# turkin_ivt23_1d_list1.net
KiCad netlist of a schematic drawn in Altium Designer
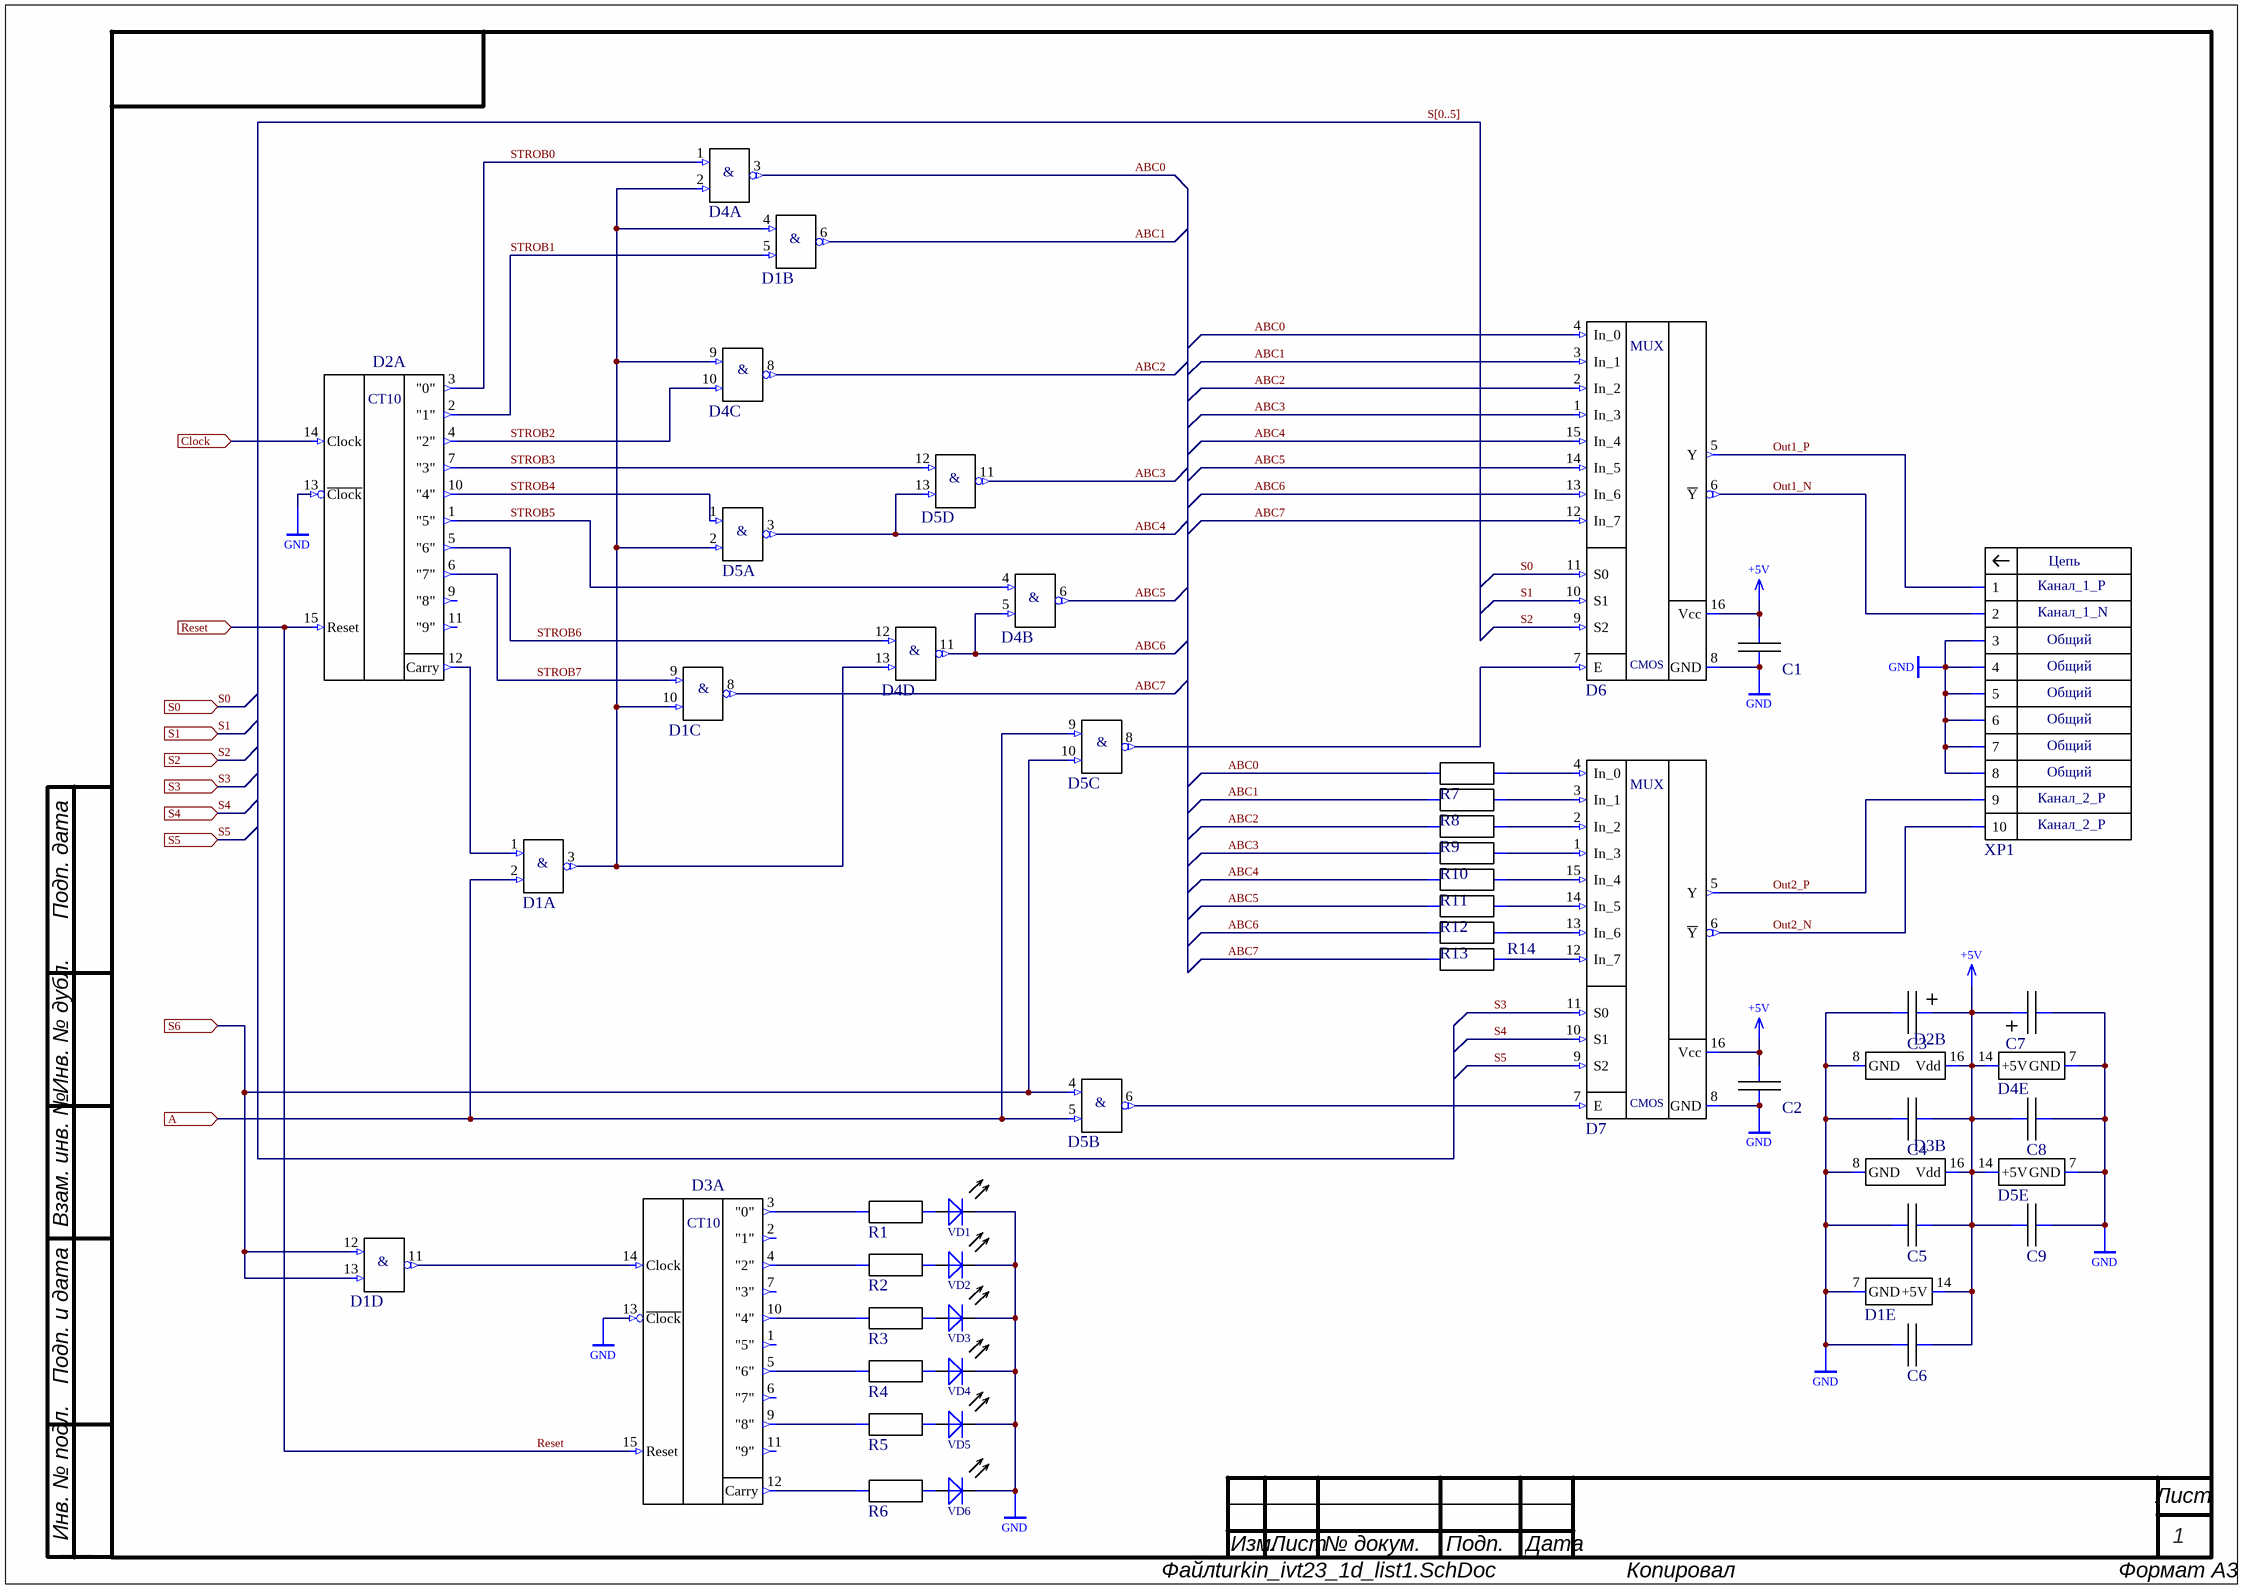
[diagram p0: turkin_ivt23_1d_list1.SchDoc]

(export (version "E")
  (design (tool "Eeschema 10.0.6"))
  (components
    (comp (ref "C1")
      (value "~")
      (footprint "0805_N")
      (description "Чип конденсатор 0805 Н90 ряд Е6")
      (fields
        (field (name "MANUFACTURER") "ООО \"Кулон\"")
        (field (name "TOLERANCE") "+80%-20%")
        (field (name "CREATED_BY") "Желобаев")
      )
      (libsource (lib "Int_Library_for_Lessons_3") (part "К10-79_0805_Н90"))
    )
    (comp (ref "C2")
      (value "~")
      (footprint "0805_N")
      (description "Чип конденсатор 0805 Н90 ряд Е6")
      (fields
        (field (name "MANUFACTURER") "ООО \"Кулон\"")
        (field (name "TOLERANCE") "+80%-20%")
        (field (name "CREATED_BY") "Желобаев")
      )
      (libsource (lib "Int_Library_for_Lessons_3") (part "К10-79_0805_Н90"))
    )
    (comp (ref "C3")
      (value "C")
      (footprint "C-Tantal")
      (description "К53-65 Конденсатор танталовый C(6032) 0,47-100 мкФ")
      (fields
        (field (name "VOLTAGE") "16В")
        (field (name "MANUFACTURER") "ОАО \"Элеконд\"")
        (field (name "CREATED_BY") "Желобаев")
      )
      (libsource (lib "Int_Library_for_Lessons_3") (part "K53-65_C_10%"))
    )
    (comp (ref "C4")
      (value "~")
      (footprint "0805_N")
      (description "Чип конденсатор 0805 Н90 ряд Е6")
      (fields
        (field (name "MANUFACTURER") "ООО \"Кулон\"")
        (field (name "TOLERANCE") "+80%-20%")
        (field (name "CREATED_BY") "Желобаев")
      )
      (libsource (lib "Int_Library_for_Lessons_3") (part "К10-79_0805_Н90"))
    )
    (comp (ref "C5")
      (value "~")
      (footprint "0805_N")
      (description "Чип конденсатор 0805 Н90 ряд Е6")
      (fields
        (field (name "MANUFACTURER") "ООО \"Кулон\"")
        (field (name "TOLERANCE") "+80%-20%")
        (field (name "CREATED_BY") "Желобаев")
      )
      (libsource (lib "Int_Library_for_Lessons_3") (part "К10-79_0805_Н90"))
    )
    (comp (ref "C6")
      (value "~")
      (footprint "0805_N")
      (description "Чип конденсатор 0805 Н90 ряд Е6")
      (fields
        (field (name "MANUFACTURER") "ООО \"Кулон\"")
        (field (name "TOLERANCE") "+80%-20%")
        (field (name "CREATED_BY") "Желобаев")
      )
      (libsource (lib "Int_Library_for_Lessons_3") (part "К10-79_0805_Н90"))
    )
    (comp (ref "C7")
      (value "C")
      (footprint "C-Tantal")
      (description "К53-65 Конденсатор танталовый C(6032) 0,47-100 мкФ")
      (fields
        (field (name "VOLTAGE") "16В")
        (field (name "MANUFACTURER") "ОАО \"Элеконд\"")
        (field (name "CREATED_BY") "Желобаев")
      )
      (libsource (lib "Int_Library_for_Lessons_3") (part "K53-65_C_10%"))
    )
    (comp (ref "C8")
      (value "~")
      (footprint "0805_N")
      (description "Чип конденсатор 0805 Н90 ряд Е6")
      (fields
        (field (name "MANUFACTURER") "ООО \"Кулон\"")
        (field (name "TOLERANCE") "+80%-20%")
        (field (name "CREATED_BY") "Желобаев")
      )
      (libsource (lib "Int_Library_for_Lessons_3") (part "К10-79_0805_Н90"))
    )
    (comp (ref "C9")
      (value "~")
      (footprint "0805_N")
      (description "Чип конденсатор 0805 Н90 ряд Е6")
      (fields
        (field (name "MANUFACTURER") "ООО \"Кулон\"")
        (field (name "TOLERANCE") "+80%-20%")
        (field (name "CREATED_BY") "Желобаев")
      )
      (libsource (lib "Int_Library_for_Lessons_3") (part "К10-79_0805_Н90"))
    )
    (comp (ref "D1")
      (value "74AC00SC")
      (footprint "SO14-N")
      (description "4 элемента 2И-НЕ TTL SOIC-14")
      (fields (field (name "MANUFACTURER") "ON Semiconductor") (field (name "CREATED_BY") "Желобаев"))
      (libsource (lib "Int_Library_for_Lessons_3") (part "74AC00SC"))
    )
    (comp (ref "D2")
      (value "DIP-16")
      (footprint "DIP16")
      (description "Декадный счетчик c 10 декодированными выходами")
      (fields (field (name "MANUFACTURER") "STMicroelectronics") (field (name "CREATED_BY") "Желобаев"))
      (libsource (lib "Int_Library_for_Lessons_3") (part "HCF4017BEY"))
    )
    (comp (ref "D3")
      (value "DIP-16")
      (footprint "DIP16")
      (description "Декадный счетчик c 10 декодированными выходами")
      (fields (field (name "MANUFACTURER") "STMicroelectronics") (field (name "CREATED_BY") "Желобаев"))
      (libsource (lib "Int_Library_for_Lessons_3") (part "HCF4017BEY"))
    )
    (comp (ref "D4")
      (value "74AC00SC")
      (footprint "SO14-N")
      (description "4 элемента 2И-НЕ TTL SOIC-14")
      (fields (field (name "MANUFACTURER") "ON Semiconductor") (field (name "CREATED_BY") "Желобаев"))
      (libsource (lib "Int_Library_for_Lessons_3") (part "74AC00SC"))
    )
    (comp (ref "D5")
      (value "74AC00SC")
      (footprint "SO14-N")
      (description "4 элемента 2И-НЕ TTL SOIC-14")
      (fields (field (name "MANUFACTURER") "ON Semiconductor") (field (name "CREATED_BY") "Желобаев"))
      (libsource (lib "Int_Library_for_Lessons_3") (part "74AC00SC"))
    )
    (comp (ref "D6")
      (value "SOIC-16")
      (footprint "SO16-N")
      (description "мультиплексор 8 канальный CMOS")
      (fields (field (name "MANUFACTURER") "NXP Semiconductors") (field (name "CREATED_BY") "Желобаев"))
      (libsource (lib "Int_Library_for_Lessons_3") (part "74HC151D"))
    )
    (comp (ref "D7")
      (value "SOIC-16")
      (footprint "SO16-N")
      (description "мультиплексор 8 канальный CMOS")
      (fields (field (name "MANUFACTURER") "NXP Semiconductors") (field (name "CREATED_BY") "Желобаев"))
      (libsource (lib "Int_Library_for_Lessons_3") (part "74HC151D"))
    )
    (comp (ref "R1")
      (value "0805")
      (footprint "RES_0805_2012_N")
      (description "Резистор от 0,75 Ом до 2 МОм")
      (fields
        (field (name "MANUFACTURER") "ОАО \"НПО \"Эркон\"")
        (field (name "TOLERANCE") "5%")
        (field (name "CREATED_BY") "Желобаев")
      )
      (libsource (lib "Int_Library_for_Lessons_3") (part "Р1-12-0,125-5%"))
    )
    (comp (ref "R2")
      (value "0805")
      (footprint "RES_0805_2012_N")
      (description "Резистор от 0,75 Ом до 2 МОм")
      (fields
        (field (name "MANUFACTURER") "ОАО \"НПО \"Эркон\"")
        (field (name "TOLERANCE") "5%")
        (field (name "CREATED_BY") "Желобаев")
      )
      (libsource (lib "Int_Library_for_Lessons_3") (part "Р1-12-0,125-5%"))
    )
    (comp (ref "R3")
      (value "0805")
      (footprint "RES_0805_2012_N")
      (description "Резистор от 0,75 Ом до 2 МОм")
      (fields
        (field (name "MANUFACTURER") "ОАО \"НПО \"Эркон\"")
        (field (name "TOLERANCE") "5%")
        (field (name "CREATED_BY") "Желобаев")
      )
      (libsource (lib "Int_Library_for_Lessons_3") (part "Р1-12-0,125-5%"))
    )
    (comp (ref "R4")
      (value "0805")
      (footprint "RES_0805_2012_N")
      (description "Резистор от 0,75 Ом до 2 МОм")
      (fields
        (field (name "MANUFACTURER") "ОАО \"НПО \"Эркон\"")
        (field (name "TOLERANCE") "5%")
        (field (name "CREATED_BY") "Желобаев")
      )
      (libsource (lib "Int_Library_for_Lessons_3") (part "Р1-12-0,125-5%"))
    )
    (comp (ref "R5")
      (value "0805")
      (footprint "RES_0805_2012_N")
      (description "Резистор от 0,75 Ом до 2 МОм")
      (fields
        (field (name "MANUFACTURER") "ОАО \"НПО \"Эркон\"")
        (field (name "TOLERANCE") "5%")
        (field (name "CREATED_BY") "Желобаев")
      )
      (libsource (lib "Int_Library_for_Lessons_3") (part "Р1-12-0,125-5%"))
    )
    (comp (ref "R6")
      (value "0805")
      (footprint "RES_0805_2012_N")
      (description "Резистор от 0,75 Ом до 2 МОм")
      (fields
        (field (name "MANUFACTURER") "ОАО \"НПО \"Эркон\"")
        (field (name "TOLERANCE") "5%")
        (field (name "CREATED_BY") "Желобаев")
      )
      (libsource (lib "Int_Library_for_Lessons_3") (part "Р1-12-0,125-5%"))
    )
    (comp (ref "R7")
      (value "0805")
      (footprint "RES_0805_2012_N")
      (description "Резистор от 0,75 Ом до 2 МОм")
      (fields
        (field (name "MANUFACTURER") "ОАО \"НПО \"Эркон\"")
        (field (name "TOLERANCE") "5%")
        (field (name "CREATED_BY") "Желобаев")
      )
      (libsource (lib "Int_Library_for_Lessons_3") (part "Р1-12-0,125-5%"))
    )
    (comp (ref "R8")
      (value "0805")
      (footprint "RES_0805_2012_N")
      (description "Резистор от 0,75 Ом до 2 МОм")
      (fields
        (field (name "MANUFACTURER") "ОАО \"НПО \"Эркон\"")
        (field (name "TOLERANCE") "5%")
        (field (name "CREATED_BY") "Желобаев")
      )
      (libsource (lib "Int_Library_for_Lessons_3") (part "Р1-12-0,125-5%"))
    )
    (comp (ref "R9")
      (value "0805")
      (footprint "RES_0805_2012_N")
      (description "Резистор от 0,75 Ом до 2 МОм")
      (fields
        (field (name "MANUFACTURER") "ОАО \"НПО \"Эркон\"")
        (field (name "TOLERANCE") "5%")
        (field (name "CREATED_BY") "Желобаев")
      )
      (libsource (lib "Int_Library_for_Lessons_3") (part "Р1-12-0,125-5%"))
    )
    (comp (ref "R10")
      (value "0805")
      (footprint "RES_0805_2012_N")
      (description "Резистор от 0,75 Ом до 2 МОм")
      (fields
        (field (name "MANUFACTURER") "ОАО \"НПО \"Эркон\"")
        (field (name "TOLERANCE") "5%")
        (field (name "CREATED_BY") "Желобаев")
      )
      (libsource (lib "Int_Library_for_Lessons_3") (part "Р1-12-0,125-5%"))
    )
    (comp (ref "R11")
      (value "0805")
      (footprint "RES_0805_2012_N")
      (description "Резистор от 0,75 Ом до 2 МОм")
      (fields
        (field (name "MANUFACTURER") "ОАО \"НПО \"Эркон\"")
        (field (name "TOLERANCE") "5%")
        (field (name "CREATED_BY") "Желобаев")
      )
      (libsource (lib "Int_Library_for_Lessons_3") (part "Р1-12-0,125-5%"))
    )
    (comp (ref "R12")
      (value "0805")
      (footprint "RES_0805_2012_N")
      (description "Резистор от 0,75 Ом до 2 МОм")
      (fields
        (field (name "MANUFACTURER") "ОАО \"НПО \"Эркон\"")
        (field (name "TOLERANCE") "5%")
        (field (name "CREATED_BY") "Желобаев")
      )
      (libsource (lib "Int_Library_for_Lessons_3") (part "Р1-12-0,125-5%"))
    )
    (comp (ref "R13")
      (value "0805")
      (footprint "RES_0805_2012_N")
      (description "Резистор от 0,75 Ом до 2 МОм")
      (fields
        (field (name "MANUFACTURER") "ОАО \"НПО \"Эркон\"")
        (field (name "TOLERANCE") "5%")
        (field (name "CREATED_BY") "Желобаев")
      )
      (libsource (lib "Int_Library_for_Lessons_3") (part "Р1-12-0,125-5%"))
    )
    (comp (ref "R14")
      (value "0805")
      (footprint "RES_0805_2012_N")
      (description "Резистор от 0,75 Ом до 2 МОм")
      (fields
        (field (name "MANUFACTURER") "ОАО \"НПО \"Эркон\"")
        (field (name "TOLERANCE") "5%")
        (field (name "CREATED_BY") "Желобаев")
      )
      (libsource (lib "Int_Library_for_Lessons_3") (part "Р1-12-0,125-5%"))
    )
    (comp (ref "VD1")
      (value "521-9466")
      (footprint "added_pcb:521-9466")
      (description "Светодиод 5мм желтый")
      (libsource (lib "added_elements") (part "521-9466"))
    )
    (comp (ref "VD2")
      (value "521-9466")
      (footprint "added_pcb:521-9466")
      (description "Светодиод 5мм желтый")
      (libsource (lib "added_elements") (part "521-9466"))
    )
    (comp (ref "VD3")
      (value "521-9466")
      (footprint "added_pcb:521-9466")
      (description "Светодиод 5мм желтый")
      (libsource (lib "added_elements") (part "521-9466"))
    )
    (comp (ref "VD4")
      (value "521-9466")
      (footprint "added_pcb:521-9466")
      (description "Светодиод 5мм желтый")
      (libsource (lib "added_elements") (part "521-9466"))
    )
    (comp (ref "VD5")
      (value "521-9466")
      (footprint "added_pcb:521-9466")
      (description "Светодиод 5мм желтый")
      (libsource (lib "added_elements") (part "521-9466"))
    )
    (comp (ref "VD6")
      (value "521-9466")
      (footprint "added_pcb:521-9466")
      (description "Светодиод 5мм желтый")
      (libsource (lib "added_elements") (part "521-9466"))
    )
    (comp (ref "XP1")
      (value "TE_1-1634689-0")
      (footprint "BH-10R")
      (description "Вилка типа BH-10R угловая правая двухрядная 2х5х2.54")
      (fields (field (name "MANUFACTURER") "TE Connectivity") (field (name "CREATED_BY") "Желобаев"))
      (libsource (lib "Int_Library_for_Lessons_3") (part "TE_1-1634689-0"))
    )
  )
  (nets
    (net (code "1") (name "+5V") (class "Default")
      (node (ref "C1") (pin "2") (pinfunction "2_2") (pintype "passive"))
      (node (ref "C2") (pin "2") (pinfunction "2_2") (pintype "passive"))
      (node (ref "C3") (pin "+") (pinfunction "+_+") (pintype "passive"))
      (node (ref "C4") (pin "1") (pinfunction "1_1") (pintype "passive"))
      (node (ref "C5") (pin "1") (pinfunction "1_1") (pintype "passive"))
      (node (ref "C6") (pin "1") (pinfunction "1_1") (pintype "passive"))
      (node (ref "C7") (pin "+") (pinfunction "+_+") (pintype "passive"))
      (node (ref "C8") (pin "2") (pinfunction "2_2") (pintype "passive"))
      (node (ref "C9") (pin "2") (pinfunction "2_2") (pintype "passive"))
      (node (ref "D1") (pin "14") (pinfunction "+5V_14") (pintype "power_in"))
      (node (ref "D2") (pin "16") (pinfunction "Vdd_16") (pintype "power_in"))
      (node (ref "D3") (pin "16") (pinfunction "Vdd_16") (pintype "power_in"))
      (node (ref "D4") (pin "14") (pinfunction "+5V_14") (pintype "power_in"))
      (node (ref "D5") (pin "14") (pinfunction "+5V_14") (pintype "power_in"))
      (node (ref "D6") (pin "16") (pinfunction "Vcc_16") (pintype "power_in"))
      (node (ref "D7") (pin "16") (pinfunction "Vcc_16") (pintype "power_in"))
    )
    (net (code "2") (name "/A") (class "Default")
      (node (ref "D1") (pin "2") (pinfunction "In2_2") (pintype "input"))
      (node (ref "D5") (pin "5") (pinfunction "In2_5") (pintype "input"))
      (node (ref "D5") (pin "9") (pinfunction "In1_9") (pintype "input"))
    )
    (net (code "3") (name "/ABC0") (class "Default")
      (node (ref "D4") (pin "3") (pinfunction "Out_3") (pintype "output"))
      (node (ref "D6") (pin "4") (pinfunction "In_0_4") (pintype "input"))
      (node (ref "R7") (pin "1") (pinfunction "1_1") (pintype "passive"))
    )
    (net (code "4") (name "/ABC1") (class "Default")
      (node (ref "D1") (pin "6") (pinfunction "Out_6") (pintype "output"))
      (node (ref "D6") (pin "3") (pinfunction "In_1_3") (pintype "input"))
      (node (ref "R8") (pin "1") (pinfunction "1_1") (pintype "passive"))
    )
    (net (code "5") (name "/ABC2") (class "Default")
      (node (ref "D4") (pin "8") (pinfunction "Out_8") (pintype "output"))
      (node (ref "D6") (pin "2") (pinfunction "In_2_2") (pintype "input"))
      (node (ref "R9") (pin "1") (pinfunction "1_1") (pintype "passive"))
    )
    (net (code "6") (name "/ABC3") (class "Default")
      (node (ref "D5") (pin "11") (pinfunction "Out_11") (pintype "output"))
      (node (ref "D6") (pin "1") (pinfunction "In_3_1") (pintype "input"))
      (node (ref "R10") (pin "1") (pinfunction "1_1") (pintype "passive"))
    )
    (net (code "7") (name "/ABC4") (class "Default")
      (node (ref "D5") (pin "13") (pinfunction "In2_13") (pintype "input"))
      (node (ref "D5") (pin "3") (pinfunction "Out_3") (pintype "output"))
      (node (ref "D6") (pin "15") (pinfunction "In_4_15") (pintype "input"))
      (node (ref "R11") (pin "1") (pinfunction "1_1") (pintype "passive"))
    )
    (net (code "8") (name "/ABC5") (class "Default")
      (node (ref "D4") (pin "6") (pinfunction "Out_6") (pintype "output"))
      (node (ref "D6") (pin "14") (pinfunction "In_5_14") (pintype "input"))
      (node (ref "R12") (pin "1") (pinfunction "1_1") (pintype "passive"))
    )
    (net (code "9") (name "/ABC6") (class "Default")
      (node (ref "D4") (pin "11") (pinfunction "Out_11") (pintype "output"))
      (node (ref "D4") (pin "5") (pinfunction "In2_5") (pintype "input"))
      (node (ref "D6") (pin "13") (pinfunction "In_6_13") (pintype "input"))
      (node (ref "R13") (pin "1") (pinfunction "1_1") (pintype "passive"))
    )
    (net (code "10") (name "/ABC7") (class "Default")
      (node (ref "D1") (pin "8") (pinfunction "Out_8") (pintype "output"))
      (node (ref "D6") (pin "12") (pinfunction "In_7_12") (pintype "input"))
      (node (ref "R14") (pin "1") (pinfunction "1_1") (pintype "passive"))
    )
    (net (code "11") (name "/Clock") (class "Default")
      (node (ref "D2") (pin "14") (pinfunction "Clock_14") (pintype "input"))
    )
    (net (code "12") (name "/Out1_N") (class "Default")
      (node (ref "D6") (pin "6") (pinfunction "Y_6") (pintype "output"))
      (node (ref "XP1") (pin "2") (pinfunction "2_2") (pintype "passive"))
    )
    (net (code "13") (name "/Out1_P") (class "Default")
      (node (ref "D6") (pin "5") (pinfunction "Y_5") (pintype "output"))
      (node (ref "XP1") (pin "1") (pinfunction "1_1") (pintype "passive"))
    )
    (net (code "14") (name "/Out2_N") (class "Default")
      (node (ref "D7") (pin "6") (pinfunction "Y_6") (pintype "output"))
      (node (ref "XP1") (pin "10") (pinfunction "10_10") (pintype "passive"))
    )
    (net (code "15") (name "/Out2_P") (class "Default")
      (node (ref "D7") (pin "5") (pinfunction "Y_5") (pintype "output"))
      (node (ref "XP1") (pin "9") (pinfunction "9_9") (pintype "passive"))
    )
    (net (code "16") (name "/Reset") (class "Default")
      (node (ref "D2") (pin "15") (pinfunction "Reset_15") (pintype "input"))
      (node (ref "D3") (pin "15") (pinfunction "Reset_15") (pintype "input"))
    )
    (net (code "17") (name "/S0") (class "Default")
      (node (ref "D6") (pin "11") (pinfunction "S0_11") (pintype "input"))
    )
    (net (code "18") (name "/S1") (class "Default")
      (node (ref "D6") (pin "10") (pinfunction "S1_10") (pintype "input"))
    )
    (net (code "19") (name "/S2") (class "Default")
      (node (ref "D6") (pin "9") (pinfunction "S2_9") (pintype "input"))
    )
    (net (code "20") (name "/S3") (class "Default")
      (node (ref "D7") (pin "11") (pinfunction "S0_11") (pintype "input"))
    )
    (net (code "21") (name "/S4") (class "Default")
      (node (ref "D7") (pin "10") (pinfunction "S1_10") (pintype "input"))
    )
    (net (code "22") (name "/S5") (class "Default")
      (node (ref "D7") (pin "9") (pinfunction "S2_9") (pintype "input"))
    )
    (net (code "23") (name "/S6") (class "Default")
      (node (ref "D1") (pin "12") (pinfunction "In1_12") (pintype "input"))
      (node (ref "D1") (pin "13") (pinfunction "In2_13") (pintype "input"))
      (node (ref "D5") (pin "10") (pinfunction "In2_10") (pintype "input"))
      (node (ref "D5") (pin "4") (pinfunction "In1_4") (pintype "input"))
    )
    (net (code "24") (name "/STROB0") (class "Default")
      (node (ref "D2") (pin "3") (pinfunction "\"0\"_3") (pintype "output"))
      (node (ref "D4") (pin "1") (pinfunction "In1_1") (pintype "input"))
    )
    (net (code "25") (name "/STROB1") (class "Default")
      (node (ref "D1") (pin "5") (pinfunction "In2_5") (pintype "input"))
      (node (ref "D2") (pin "2") (pinfunction "\"1\"_2") (pintype "output"))
    )
    (net (code "26") (name "/STROB2") (class "Default")
      (node (ref "D2") (pin "4") (pinfunction "\"2\"_4") (pintype "output"))
      (node (ref "D4") (pin "10") (pinfunction "In2_10") (pintype "input"))
    )
    (net (code "27") (name "/STROB3") (class "Default")
      (node (ref "D2") (pin "7") (pinfunction "\"3\"_7") (pintype "output"))
      (node (ref "D5") (pin "12") (pinfunction "In1_12") (pintype "input"))
    )
    (net (code "28") (name "/STROB4") (class "Default")
      (node (ref "D2") (pin "10") (pinfunction "\"4\"_10") (pintype "output"))
      (node (ref "D5") (pin "1") (pinfunction "In1_1") (pintype "input"))
    )
    (net (code "29") (name "/STROB5") (class "Default")
      (node (ref "D2") (pin "1") (pinfunction "\"5\"_1") (pintype "output"))
      (node (ref "D4") (pin "4") (pinfunction "In1_4") (pintype "input"))
    )
    (net (code "30") (name "/STROB6") (class "Default")
      (node (ref "D2") (pin "5") (pinfunction "\"6\"_5") (pintype "output"))
      (node (ref "D4") (pin "12") (pinfunction "In1_12") (pintype "input"))
    )
    (net (code "31") (name "/STROB7") (class "Default")
      (node (ref "D1") (pin "9") (pinfunction "In1_9") (pintype "input"))
      (node (ref "D2") (pin "6") (pinfunction "\"7\"_6") (pintype "output"))
    )
    (net (code "33") (name "GND") (class "Default")
      (node (ref "C1") (pin "1") (pinfunction "1_1") (pintype "passive"))
      (node (ref "C2") (pin "1") (pinfunction "1_1") (pintype "passive"))
      (node (ref "C3") (pin "-") (pinfunction "-_-") (pintype "passive"))
      (node (ref "C4") (pin "2") (pinfunction "2_2") (pintype "passive"))
      (node (ref "C5") (pin "2") (pinfunction "2_2") (pintype "passive"))
      (node (ref "C6") (pin "2") (pinfunction "2_2") (pintype "passive"))
      (node (ref "C7") (pin "-") (pinfunction "-_-") (pintype "passive"))
      (node (ref "C8") (pin "1") (pinfunction "1_1") (pintype "passive"))
      (node (ref "C9") (pin "1") (pinfunction "1_1") (pintype "passive"))
      (node (ref "D1") (pin "7") (pinfunction "GND_7") (pintype "power_in"))
      (node (ref "D2") (pin "13") (pinfunction "Clock_13") (pintype "input"))
      (node (ref "D2") (pin "8") (pinfunction "GND_8") (pintype "power_in"))
      (node (ref "D3") (pin "13") (pinfunction "Clock_13") (pintype "input"))
      (node (ref "D3") (pin "8") (pinfunction "GND_8") (pintype "power_in"))
      (node (ref "D4") (pin "7") (pinfunction "GND_7") (pintype "power_in"))
      (node (ref "D5") (pin "7") (pinfunction "GND_7") (pintype "power_in"))
      (node (ref "D6") (pin "8") (pinfunction "GND_8") (pintype "power_in"))
      (node (ref "D7") (pin "8") (pinfunction "GND_8") (pintype "power_in"))
      (node (ref "VD1") (pin "C") (pinfunction "C_C") (pintype "passive"))
      (node (ref "VD2") (pin "C") (pinfunction "C_C") (pintype "passive"))
      (node (ref "VD3") (pin "C") (pinfunction "C_C") (pintype "passive"))
      (node (ref "VD4") (pin "C") (pinfunction "C_C") (pintype "passive"))
      (node (ref "VD5") (pin "C") (pinfunction "C_C") (pintype "passive"))
      (node (ref "VD6") (pin "C") (pinfunction "C_C") (pintype "passive"))
      (node (ref "XP1") (pin "3") (pinfunction "3_3") (pintype "passive"))
      (node (ref "XP1") (pin "4") (pinfunction "4_4") (pintype "passive"))
      (node (ref "XP1") (pin "5") (pinfunction "5_5") (pintype "passive"))
      (node (ref "XP1") (pin "6") (pinfunction "6_6") (pintype "passive"))
      (node (ref "XP1") (pin "7") (pinfunction "7_7") (pintype "passive"))
      (node (ref "XP1") (pin "8") (pinfunction "8_8") (pintype "passive"))
    )
    (net (code "34") (name "Net-(D1A-In1)") (class "Default")
      (node (ref "D1") (pin "1") (pinfunction "In1_1") (pintype "input"))
      (node (ref "D2") (pin "12") (pinfunction "Carry_12") (pintype "output"))
    )
    (net (code "35") (name "Net-(D1A-Out)") (class "Default")
      (node (ref "D1") (pin "10") (pinfunction "In2_10") (pintype "input"))
      (node (ref "D1") (pin "3") (pinfunction "Out_3") (pintype "output"))
      (node (ref "D1") (pin "4") (pinfunction "In1_4") (pintype "input"))
      (node (ref "D4") (pin "13") (pinfunction "In2_13") (pintype "input"))
      (node (ref "D4") (pin "2") (pinfunction "In2_2") (pintype "input"))
      (node (ref "D4") (pin "9") (pinfunction "In1_9") (pintype "input"))
      (node (ref "D5") (pin "2") (pinfunction "In2_2") (pintype "input"))
    )
    (net (code "36") (name "Net-(D1D-Out)") (class "Default")
      (node (ref "D1") (pin "11") (pinfunction "Out_11") (pintype "output"))
      (node (ref "D3") (pin "14") (pinfunction "Clock_14") (pintype "input"))
    )
    (net (code "37") (name "Net-(D3A-\"0\")") (class "Default")
      (node (ref "D3") (pin "3") (pinfunction "\"0\"_3") (pintype "output"))
      (node (ref "R1") (pin "1") (pinfunction "1_1") (pintype "passive"))
    )
    (net (code "38") (name "Net-(D3A-\"2\")") (class "Default")
      (node (ref "D3") (pin "4") (pinfunction "\"2\"_4") (pintype "output"))
      (node (ref "R2") (pin "1") (pinfunction "1_1") (pintype "passive"))
    )
    (net (code "39") (name "Net-(D3A-\"4\")") (class "Default")
      (node (ref "D3") (pin "10") (pinfunction "\"4\"_10") (pintype "output"))
      (node (ref "R3") (pin "1") (pinfunction "1_1") (pintype "passive"))
    )
    (net (code "40") (name "Net-(D3A-\"6\")") (class "Default")
      (node (ref "D3") (pin "5") (pinfunction "\"6\"_5") (pintype "output"))
      (node (ref "R4") (pin "1") (pinfunction "1_1") (pintype "passive"))
    )
    (net (code "41") (name "Net-(D3A-\"8\")") (class "Default")
      (node (ref "D3") (pin "9") (pinfunction "\"8\"_9") (pintype "output"))
      (node (ref "R5") (pin "1") (pinfunction "1_1") (pintype "passive"))
    )
    (net (code "42") (name "Net-(D3A-Carry)") (class "Default")
      (node (ref "D3") (pin "12") (pinfunction "Carry_12") (pintype "output"))
      (node (ref "R6") (pin "1") (pinfunction "1_1") (pintype "passive"))
    )
    (net (code "43") (name "Net-(D5B-Out)") (class "Default")
      (node (ref "D5") (pin "6") (pinfunction "Out_6") (pintype "output"))
      (node (ref "D7") (pin "7") (pinfunction "E_7") (pintype "input"))
    )
    (net (code "44") (name "Net-(D5C-Out)") (class "Default")
      (node (ref "D5") (pin "8") (pinfunction "Out_8") (pintype "output"))
      (node (ref "D6") (pin "7") (pinfunction "E_7") (pintype "input"))
    )
    (net (code "45") (name "Net-(D7-In_0)") (class "Default")
      (node (ref "D7") (pin "4") (pinfunction "In_0_4") (pintype "input"))
      (node (ref "R7") (pin "2") (pinfunction "2_2") (pintype "passive"))
    )
    (net (code "46") (name "Net-(D7-In_1)") (class "Default")
      (node (ref "D7") (pin "3") (pinfunction "In_1_3") (pintype "input"))
      (node (ref "R8") (pin "2") (pinfunction "2_2") (pintype "passive"))
    )
    (net (code "47") (name "Net-(D7-In_2)") (class "Default")
      (node (ref "D7") (pin "2") (pinfunction "In_2_2") (pintype "input"))
      (node (ref "R9") (pin "2") (pinfunction "2_2") (pintype "passive"))
    )
    (net (code "48") (name "Net-(D7-In_3)") (class "Default")
      (node (ref "D7") (pin "1") (pinfunction "In_3_1") (pintype "input"))
      (node (ref "R10") (pin "2") (pinfunction "2_2") (pintype "passive"))
    )
    (net (code "49") (name "Net-(D7-In_4)") (class "Default")
      (node (ref "D7") (pin "15") (pinfunction "In_4_15") (pintype "input"))
      (node (ref "R11") (pin "2") (pinfunction "2_2") (pintype "passive"))
    )
    (net (code "50") (name "Net-(D7-In_5)") (class "Default")
      (node (ref "D7") (pin "14") (pinfunction "In_5_14") (pintype "input"))
      (node (ref "R12") (pin "2") (pinfunction "2_2") (pintype "passive"))
    )
    (net (code "51") (name "Net-(D7-In_6)") (class "Default")
      (node (ref "D7") (pin "13") (pinfunction "In_6_13") (pintype "input"))
      (node (ref "R13") (pin "2") (pinfunction "2_2") (pintype "passive"))
    )
    (net (code "52") (name "Net-(D7-In_7)") (class "Default")
      (node (ref "D7") (pin "12") (pinfunction "In_7_12") (pintype "input"))
      (node (ref "R14") (pin "2") (pinfunction "2_2") (pintype "passive"))
    )
    (net (code "53") (name "Net-(R1-Pad2)") (class "Default")
      (node (ref "R1") (pin "2") (pinfunction "2_2") (pintype "passive"))
      (node (ref "VD1") (pin "A") (pinfunction "A_A") (pintype "passive"))
    )
    (net (code "54") (name "Net-(R2-Pad2)") (class "Default")
      (node (ref "R2") (pin "2") (pinfunction "2_2") (pintype "passive"))
      (node (ref "VD2") (pin "A") (pinfunction "A_A") (pintype "passive"))
    )
    (net (code "55") (name "Net-(R3-Pad2)") (class "Default")
      (node (ref "R3") (pin "2") (pinfunction "2_2") (pintype "passive"))
      (node (ref "VD3") (pin "A") (pinfunction "A_A") (pintype "passive"))
    )
    (net (code "56") (name "Net-(R4-Pad2)") (class "Default")
      (node (ref "R4") (pin "2") (pinfunction "2_2") (pintype "passive"))
      (node (ref "VD4") (pin "A") (pinfunction "A_A") (pintype "passive"))
    )
    (net (code "57") (name "Net-(R5-Pad2)") (class "Default")
      (node (ref "R5") (pin "2") (pinfunction "2_2") (pintype "passive"))
      (node (ref "VD5") (pin "A") (pinfunction "A_A") (pintype "passive"))
    )
    (net (code "58") (name "Net-(R6-Pad2)") (class "Default")
      (node (ref "R6") (pin "2") (pinfunction "2_2") (pintype "passive"))
      (node (ref "VD6") (pin "A") (pinfunction "A_A") (pintype "passive"))
    )
    (net (code "59") (name "unconnected-(D2A-\"8\"-Pad9)") (class "Default")
      (node (ref "D2") (pin "9") (pinfunction "\"8\"_9") (pintype "output"))
    )
    (net (code "60") (name "unconnected-(D2A-\"9\"-Pad11)") (class "Default")
      (node (ref "D2") (pin "11") (pinfunction "\"9\"_11") (pintype "output"))
    )
    (net (code "61") (name "unconnected-(D3A-\"1\"-Pad2)") (class "Default")
      (node (ref "D3") (pin "2") (pinfunction "\"1\"_2") (pintype "output"))
    )
    (net (code "62") (name "unconnected-(D3A-\"3\"-Pad7)") (class "Default")
      (node (ref "D3") (pin "7") (pinfunction "\"3\"_7") (pintype "output"))
    )
    (net (code "63") (name "unconnected-(D3A-\"5\"-Pad1)") (class "Default")
      (node (ref "D3") (pin "1") (pinfunction "\"5\"_1") (pintype "output"))
    )
    (net (code "64") (name "unconnected-(D3A-\"7\"-Pad6)") (class "Default")
      (node (ref "D3") (pin "6") (pinfunction "\"7\"_6") (pintype "output"))
    )
    (net (code "65") (name "unconnected-(D3A-\"9\"-Pad11)") (class "Default")
      (node (ref "D3") (pin "11") (pinfunction "\"9\"_11") (pintype "output"))
    )
  )
)
